# OUTPUT.net
KiCad netlist of a schematic drawn in Altium Designer
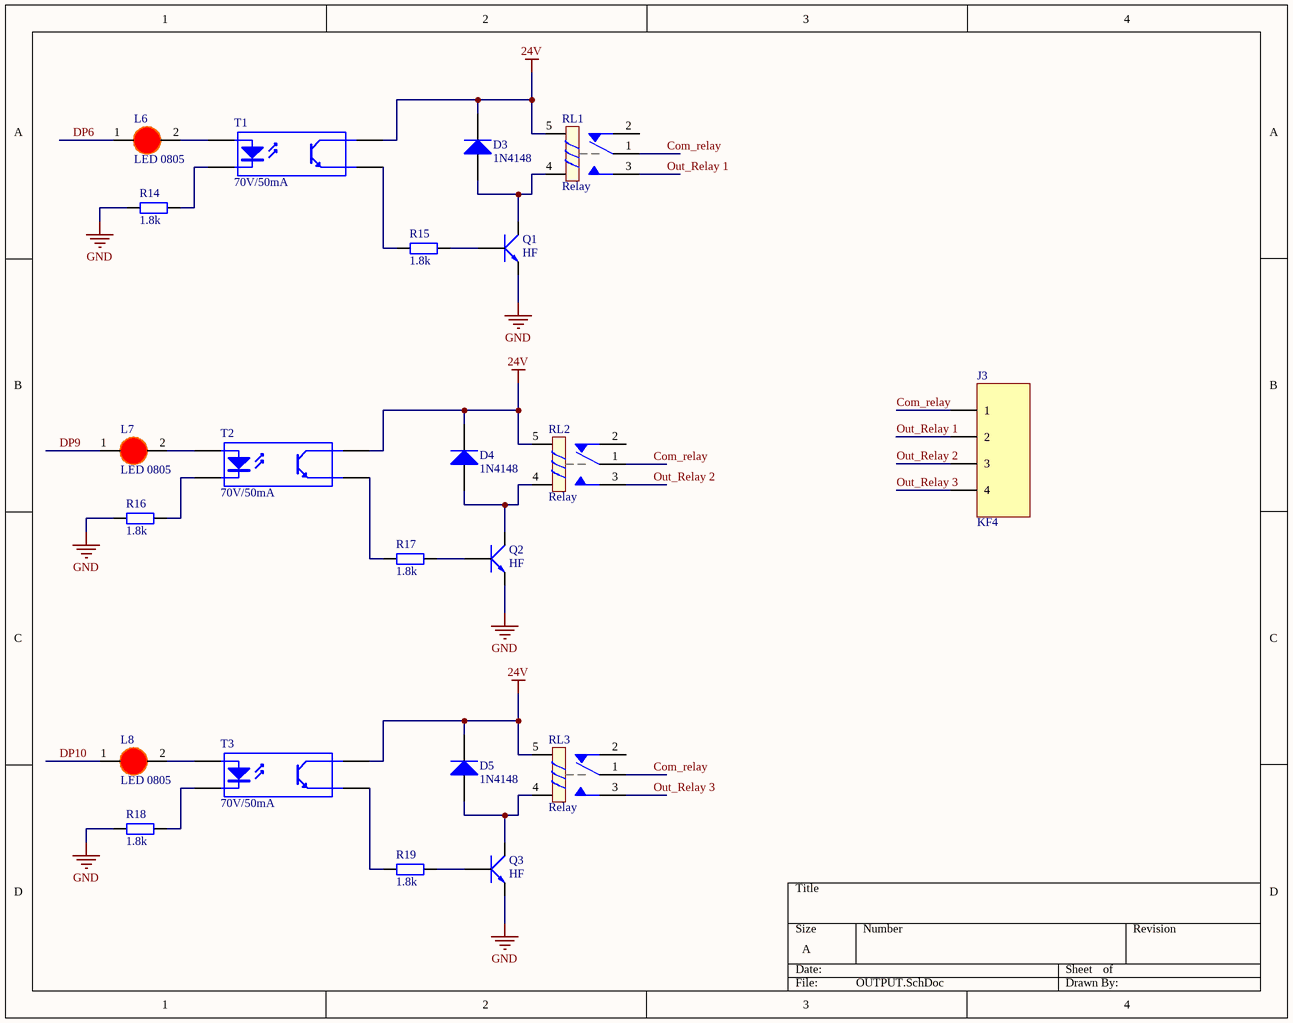
[diagram p0: OUTPUT.SchDoc]

(export (version "E")
  (design (tool "Eeschema 10.0.6"))
  (components
    (comp (ref "D3")
      (value "1N4148")
      (footprint "SOD-123")
      (description "DIODE GEN PURP 100V 300MA SOD123")
      (fields (field (name "MPN") "1N4148W-7-F") (field (name "MFR") "Diodes Incorporated"))
      (libsource (lib "BYTECH_HW_LIB_2019 (1)") (part "1N4148-W-7"))
    )
    (comp (ref "D4")
      (value "1N4148")
      (footprint "SOD-123")
      (description "DIODE GEN PURP 100V 300MA SOD123")
      (fields (field (name "MPN") "1N4148W-7-F") (field (name "MFR") "Diodes Incorporated"))
      (libsource (lib "BYTECH_HW_LIB_2019 (1)") (part "1N4148-W-7"))
    )
    (comp (ref "D5")
      (value "1N4148")
      (footprint "SOD-123")
      (description "DIODE GEN PURP 100V 300MA SOD123")
      (fields (field (name "MPN") "1N4148W-7-F") (field (name "MFR") "Diodes Incorporated"))
      (libsource (lib "BYTECH_HW_LIB_2019 (1)") (part "1N4148-W-7"))
    )
    (comp (ref "J3")
      (value "KF4")
      (footprint "KF4-5.08")
      (fields
        (field (name "MANUFACTURER") "Würth Elektronik eiSos GmbH")
        (field (name "PARTNO") "691133710004")
        (field (name "CREATED BY") "Baojun Chen")
      )
      (libsource (lib "LIBRARY1") (part "KF4"))
    )
    (comp (ref "L6")
      (value "LED 0805")
      (footprint "LED-1206-Red")
      (description "Dán")
      (libsource (lib "Altium_Lib_by_KhueNguyenCreator") (part "LED 1206 Do"))
    )
    (comp (ref "L7")
      (value "LED 0805")
      (footprint "LED-1206-Red")
      (description "Dán")
      (libsource (lib "Altium_Lib_by_KhueNguyenCreator") (part "LED 1206 Do"))
    )
    (comp (ref "L8")
      (value "LED 0805")
      (footprint "LED-1206-Red")
      (description "Dán")
      (libsource (lib "Altium_Lib_by_KhueNguyenCreator") (part "LED 1206 Do"))
    )
    (comp (ref "Q1")
      (value "HF")
      (footprint "SOT23")
      (description "NPN transistor")
      (libsource (lib "Altium_Lib_by_KhueNguyenCreator") (part "C1815 HF SMD"))
    )
    (comp (ref "Q2")
      (value "HF")
      (footprint "SOT23")
      (description "NPN transistor")
      (libsource (lib "Altium_Lib_by_KhueNguyenCreator") (part "C1815 HF SMD"))
    )
    (comp (ref "Q3")
      (value "HF")
      (footprint "SOT23")
      (description "NPN transistor")
      (libsource (lib "Altium_Lib_by_KhueNguyenCreator") (part "C1815 HF SMD"))
    )
    (comp (ref "R14")
      (value "1.8k")
      (footprint "tro smd 0805")
      (description "Dán")
      (libsource (lib "Altium_Lib_by_KhueNguyenCreator") (part "Tro 0805 5% 1.8k"))
    )
    (comp (ref "R15")
      (value "1.8k")
      (footprint "tro smd 0805")
      (description "Dán")
      (libsource (lib "Altium_Lib_by_KhueNguyenCreator") (part "Tro 0805 5% 1.8k"))
    )
    (comp (ref "R16")
      (value "1.8k")
      (footprint "tro smd 0805")
      (description "Dán")
      (libsource (lib "Altium_Lib_by_KhueNguyenCreator") (part "Tro 0805 5% 1.8k"))
    )
    (comp (ref "R17")
      (value "1.8k")
      (footprint "tro smd 0805")
      (description "Dán")
      (libsource (lib "Altium_Lib_by_KhueNguyenCreator") (part "Tro 0805 5% 1.8k"))
    )
    (comp (ref "R18")
      (value "1.8k")
      (footprint "tro smd 0805")
      (description "Dán")
      (libsource (lib "Altium_Lib_by_KhueNguyenCreator") (part "Tro 0805 5% 1.8k"))
    )
    (comp (ref "R19")
      (value "1.8k")
      (footprint "tro smd 0805")
      (description "Dán")
      (libsource (lib "Altium_Lib_by_KhueNguyenCreator") (part "Tro 0805 5% 1.8k"))
    )
    (comp (ref "RL1")
      (value "Relay")
      (footprint "Relay 5 Chan SRD")
      (description "Relay 5 Chan")
      (libsource (lib "Altium_Lib_by_KhueNguyenCreator") (part "Relay 5 Chan SRD"))
    )
    (comp (ref "RL2")
      (value "Relay")
      (footprint "Relay 5 Chan SRD")
      (description "Relay 5 Chan")
      (libsource (lib "Altium_Lib_by_KhueNguyenCreator") (part "Relay 5 Chan SRD"))
    )
    (comp (ref "RL3")
      (value "Relay")
      (footprint "Relay 5 Chan SRD")
      (description "Relay 5 Chan")
      (libsource (lib "Altium_Lib_by_KhueNguyenCreator") (part "Relay 5 Chan SRD"))
    )
    (comp (ref "T1")
      (value "70V/50mA")
      (footprint "OPTO TRANSISTOR_SMD-4")
      (description "OPTOISOLATOR 5KV TRANSISTOR 4SMD")
      (fields (field (name "MPN") "HCPL-817-500E"))
      (libsource (lib "BYTECH_HW_LIB_2019 (1)") (part "HCPL-817-500E"))
    )
    (comp (ref "T2")
      (value "70V/50mA")
      (footprint "OPTO TRANSISTOR_SMD-4")
      (description "OPTOISOLATOR 5KV TRANSISTOR 4SMD")
      (fields (field (name "MPN") "HCPL-817-500E"))
      (libsource (lib "BYTECH_HW_LIB_2019 (1)") (part "HCPL-817-500E"))
    )
    (comp (ref "T3")
      (value "70V/50mA")
      (footprint "OPTO TRANSISTOR_SMD-4")
      (description "OPTOISOLATOR 5KV TRANSISTOR 4SMD")
      (fields (field (name "MPN") "HCPL-817-500E"))
      (libsource (lib "BYTECH_HW_LIB_2019 (1)") (part "HCPL-817-500E"))
    )
  )
  (nets
    (net (code "1") (name "/Com_relay") (class "Default")
      (node (ref "J3") (pin "1") (pinfunction "1_1") (pintype "passive"))
      (node (ref "RL1") (pin "1") (pinfunction "1_1") (pintype "passive"))
      (node (ref "RL2") (pin "1") (pinfunction "1_1") (pintype "passive"))
      (node (ref "RL3") (pin "1") (pinfunction "1_1") (pintype "passive"))
    )
    (net (code "2") (name "/DP6") (class "Default")
      (node (ref "L6") (pin "1") (pinfunction "A_1") (pintype "passive"))
    )
    (net (code "3") (name "/DP9") (class "Default")
      (node (ref "L7") (pin "1") (pinfunction "A_1") (pintype "passive"))
    )
    (net (code "4") (name "/DP10") (class "Default")
      (node (ref "L8") (pin "1") (pinfunction "A_1") (pintype "passive"))
    )
    (net (code "5") (name "/Out_Relay 1") (class "Default")
      (node (ref "J3") (pin "2") (pinfunction "2_2") (pintype "passive"))
      (node (ref "RL1") (pin "3") (pinfunction "3_3") (pintype "passive"))
    )
    (net (code "6") (name "/Out_Relay 2") (class "Default")
      (node (ref "J3") (pin "3") (pinfunction "3_3") (pintype "passive"))
      (node (ref "RL2") (pin "3") (pinfunction "3_3") (pintype "passive"))
    )
    (net (code "7") (name "/Out_Relay 3") (class "Default")
      (node (ref "J3") (pin "4") (pinfunction "4_4") (pintype "passive"))
      (node (ref "RL3") (pin "3") (pinfunction "3_3") (pintype "passive"))
    )
    (net (code "8") (name "24V") (class "Default")
      (node (ref "D3") (pin "2") (pinfunction "K_2") (pintype "passive"))
      (node (ref "D4") (pin "2") (pinfunction "K_2") (pintype "passive"))
      (node (ref "D5") (pin "2") (pinfunction "K_2") (pintype "passive"))
      (node (ref "RL1") (pin "5") (pinfunction "5_5") (pintype "passive"))
      (node (ref "RL2") (pin "5") (pinfunction "5_5") (pintype "passive"))
      (node (ref "RL3") (pin "5") (pinfunction "5_5") (pintype "passive"))
      (node (ref "T1") (pin "4") (pinfunction "4_4") (pintype "passive"))
      (node (ref "T2") (pin "4") (pinfunction "4_4") (pintype "passive"))
      (node (ref "T3") (pin "4") (pinfunction "4_4") (pintype "passive"))
    )
    (net (code "9") (name "GND") (class "Default")
      (node (ref "Q1") (pin "2") (pinfunction "E_2") (pintype "passive"))
      (node (ref "Q2") (pin "2") (pinfunction "E_2") (pintype "passive"))
      (node (ref "Q3") (pin "2") (pinfunction "E_2") (pintype "passive"))
      (node (ref "R14") (pin "1") (pinfunction "1_1") (pintype "passive"))
      (node (ref "R16") (pin "1") (pinfunction "1_1") (pintype "passive"))
      (node (ref "R18") (pin "1") (pinfunction "1_1") (pintype "passive"))
    )
    (net (code "10") (name "Net-(D3-A)") (class "Default")
      (node (ref "D3") (pin "1") (pinfunction "A_1") (pintype "passive"))
      (node (ref "Q1") (pin "3") (pinfunction "C_3") (pintype "passive"))
      (node (ref "RL1") (pin "4") (pinfunction "4_4") (pintype "passive"))
    )
    (net (code "11") (name "Net-(D4-A)") (class "Default")
      (node (ref "D4") (pin "1") (pinfunction "A_1") (pintype "passive"))
      (node (ref "Q2") (pin "3") (pinfunction "C_3") (pintype "passive"))
      (node (ref "RL2") (pin "4") (pinfunction "4_4") (pintype "passive"))
    )
    (net (code "12") (name "Net-(D5-A)") (class "Default")
      (node (ref "D5") (pin "1") (pinfunction "A_1") (pintype "passive"))
      (node (ref "Q3") (pin "3") (pinfunction "C_3") (pintype "passive"))
      (node (ref "RL3") (pin "4") (pinfunction "4_4") (pintype "passive"))
    )
    (net (code "13") (name "Net-(L6-K)") (class "Default")
      (node (ref "L6") (pin "2") (pinfunction "K_2") (pintype "passive"))
      (node (ref "T1") (pin "1") (pinfunction "1_1") (pintype "passive"))
    )
    (net (code "14") (name "Net-(L7-K)") (class "Default")
      (node (ref "L7") (pin "2") (pinfunction "K_2") (pintype "passive"))
      (node (ref "T2") (pin "1") (pinfunction "1_1") (pintype "passive"))
    )
    (net (code "15") (name "Net-(L8-K)") (class "Default")
      (node (ref "L8") (pin "2") (pinfunction "K_2") (pintype "passive"))
      (node (ref "T3") (pin "1") (pinfunction "1_1") (pintype "passive"))
    )
    (net (code "16") (name "Net-(Q1-B)") (class "Default")
      (node (ref "Q1") (pin "1") (pinfunction "B_1") (pintype "passive"))
      (node (ref "R15") (pin "2") (pinfunction "2_2") (pintype "passive"))
    )
    (net (code "17") (name "Net-(Q2-B)") (class "Default")
      (node (ref "Q2") (pin "1") (pinfunction "B_1") (pintype "passive"))
      (node (ref "R17") (pin "2") (pinfunction "2_2") (pintype "passive"))
    )
    (net (code "18") (name "Net-(Q3-B)") (class "Default")
      (node (ref "Q3") (pin "1") (pinfunction "B_1") (pintype "passive"))
      (node (ref "R19") (pin "2") (pinfunction "2_2") (pintype "passive"))
    )
    (net (code "19") (name "Net-(R14-Pad2)") (class "Default")
      (node (ref "R14") (pin "2") (pinfunction "2_2") (pintype "passive"))
      (node (ref "T1") (pin "2") (pinfunction "2_2") (pintype "passive"))
    )
    (net (code "20") (name "Net-(R15-Pad1)") (class "Default")
      (node (ref "R15") (pin "1") (pinfunction "1_1") (pintype "passive"))
      (node (ref "T1") (pin "3") (pinfunction "3_3") (pintype "passive"))
    )
    (net (code "21") (name "Net-(R16-Pad2)") (class "Default")
      (node (ref "R16") (pin "2") (pinfunction "2_2") (pintype "passive"))
      (node (ref "T2") (pin "2") (pinfunction "2_2") (pintype "passive"))
    )
    (net (code "22") (name "Net-(R17-Pad1)") (class "Default")
      (node (ref "R17") (pin "1") (pinfunction "1_1") (pintype "passive"))
      (node (ref "T2") (pin "3") (pinfunction "3_3") (pintype "passive"))
    )
    (net (code "23") (name "Net-(R18-Pad2)") (class "Default")
      (node (ref "R18") (pin "2") (pinfunction "2_2") (pintype "passive"))
      (node (ref "T3") (pin "2") (pinfunction "2_2") (pintype "passive"))
    )
    (net (code "24") (name "Net-(R19-Pad1)") (class "Default")
      (node (ref "R19") (pin "1") (pinfunction "1_1") (pintype "passive"))
      (node (ref "T3") (pin "3") (pinfunction "3_3") (pintype "passive"))
    )
    (net (code "25") (name "unconnected-(RL1-Pad2)") (class "Default")
      (node (ref "RL1") (pin "2") (pinfunction "2_2") (pintype "passive"))
    )
    (net (code "26") (name "unconnected-(RL2-Pad2)") (class "Default")
      (node (ref "RL2") (pin "2") (pinfunction "2_2") (pintype "passive"))
    )
    (net (code "27") (name "unconnected-(RL3-Pad2)") (class "Default")
      (node (ref "RL3") (pin "2") (pinfunction "2_2") (pintype "passive"))
    )
  )
)
